# platine_gesamt_V05.net
KiCad netlist of a schematic drawn in EAGLE
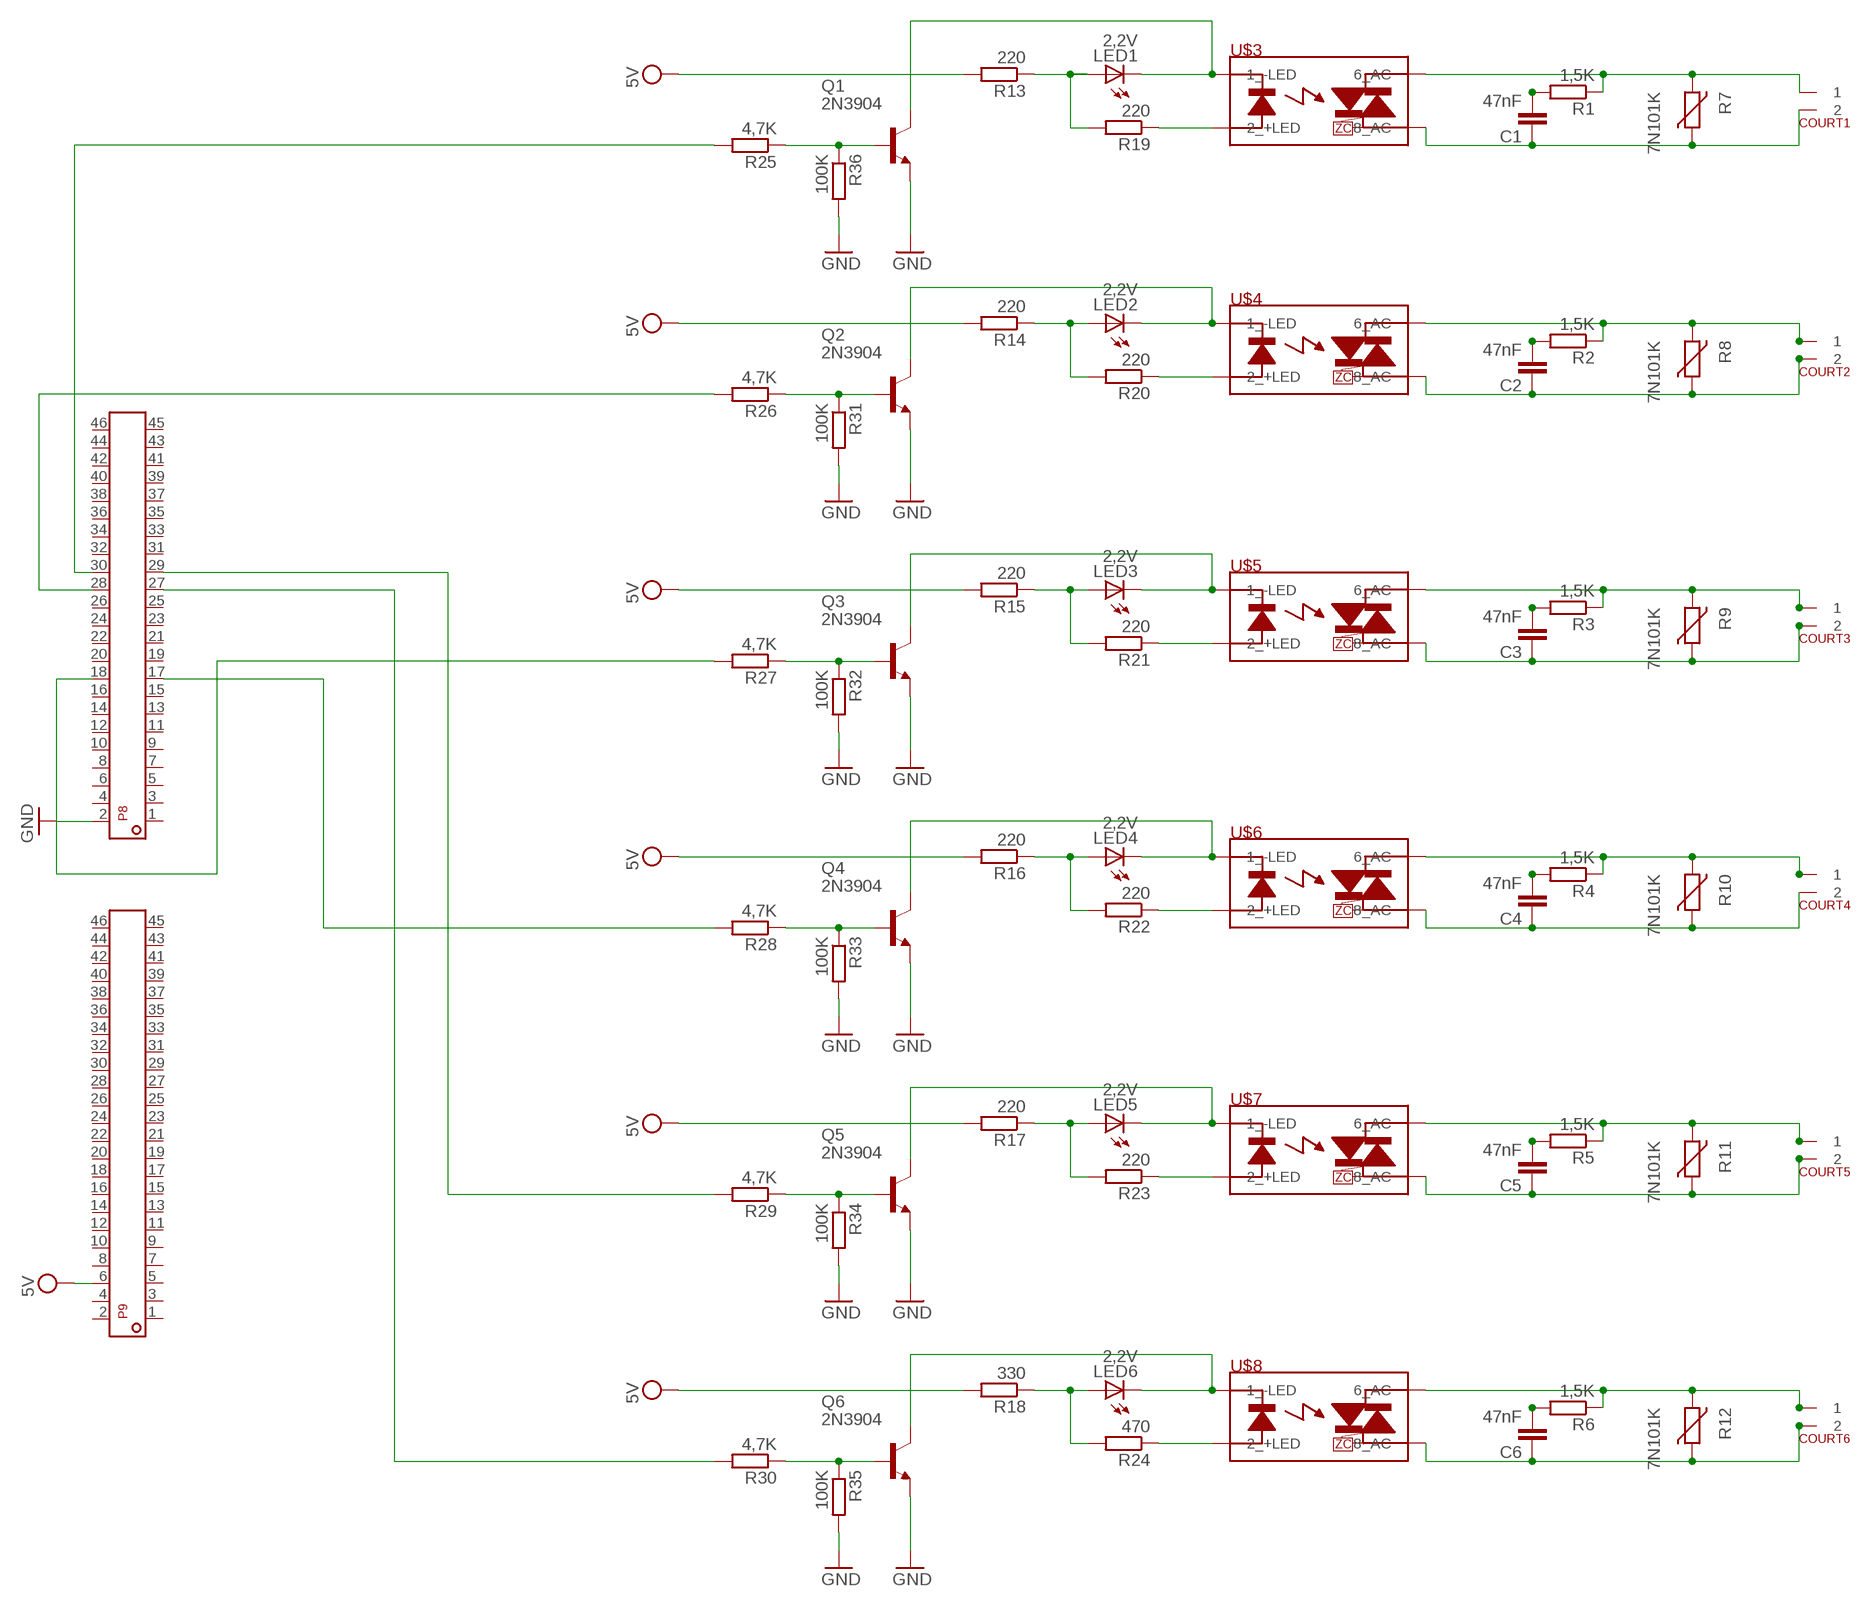
[diagram p0: schematic, sheet 1]

(export (version "E")
  (design (tool "Eeschema 10.0.6"))
  (components
    (comp (ref "C1")
      (value "47nF")
      (footprint "eagle-import:C7.5B3")
      (libsource (lib "eagle-import") (part "C7.5/3"))
    )
    (comp (ref "C2")
      (value "47nF")
      (footprint "eagle-import:C7.5B3")
      (libsource (lib "eagle-import") (part "C7.5/3"))
    )
    (comp (ref "C3")
      (value "47nF")
      (footprint "eagle-import:C7.5B3")
      (libsource (lib "eagle-import") (part "C7.5/3"))
    )
    (comp (ref "C4")
      (value "47nF")
      (footprint "eagle-import:C7.5B3")
      (libsource (lib "eagle-import") (part "C7.5/3"))
    )
    (comp (ref "C5")
      (value "47nF")
      (footprint "eagle-import:C7.5B3")
      (libsource (lib "eagle-import") (part "C7.5/3"))
    )
    (comp (ref "C6")
      (value "47nF")
      (footprint "eagle-import:C7.5B3")
      (libsource (lib "eagle-import") (part "C7.5/3"))
    )
    (comp (ref "COURT1")
      (value "KLEMMENBLOCK_2POL")
      (footprint "eagle-import:KLEMMENBLOCK_2POL")
      (libsource (lib "eagle-import") (part "KLEMMENBLOCK_2POL"))
    )
    (comp (ref "COURT2")
      (value "KLEMMENBLOCK_2POL")
      (footprint "eagle-import:KLEMMENBLOCK_2POL")
      (libsource (lib "eagle-import") (part "KLEMMENBLOCK_2POL"))
    )
    (comp (ref "COURT3")
      (value "KLEMMENBLOCK_2POL")
      (footprint "eagle-import:KLEMMENBLOCK_2POL")
      (libsource (lib "eagle-import") (part "KLEMMENBLOCK_2POL"))
    )
    (comp (ref "COURT4")
      (value "KLEMMENBLOCK_2POL")
      (footprint "eagle-import:KLEMMENBLOCK_2POL")
      (libsource (lib "eagle-import") (part "KLEMMENBLOCK_2POL"))
    )
    (comp (ref "COURT5")
      (value "KLEMMENBLOCK_2POL")
      (footprint "eagle-import:KLEMMENBLOCK_2POL")
      (libsource (lib "eagle-import") (part "KLEMMENBLOCK_2POL"))
    )
    (comp (ref "COURT6")
      (value "KLEMMENBLOCK_2POL")
      (footprint "eagle-import:KLEMMENBLOCK_2POL")
      (libsource (lib "eagle-import") (part "KLEMMENBLOCK_2POL"))
    )
    (comp (ref "LED1")
      (value "2,2V")
      (footprint "eagle-import:LED5MM")
      (libsource (lib "eagle-import") (part "LED5MM"))
    )
    (comp (ref "LED2")
      (value "2,2V")
      (footprint "eagle-import:LED5MM")
      (libsource (lib "eagle-import") (part "LED5MM"))
    )
    (comp (ref "LED3")
      (value "2,2V")
      (footprint "eagle-import:LED5MM")
      (libsource (lib "eagle-import") (part "LED5MM"))
    )
    (comp (ref "LED4")
      (value "2,2V")
      (footprint "eagle-import:LED5MM")
      (libsource (lib "eagle-import") (part "LED5MM"))
    )
    (comp (ref "LED5")
      (value "2,2V")
      (footprint "eagle-import:LED5MM")
      (libsource (lib "eagle-import") (part "LED5MM"))
    )
    (comp (ref "LED6")
      (value "2,2V")
      (footprint "eagle-import:LED5MM")
      (libsource (lib "eagle-import") (part "LED5MM"))
    )
    (comp (ref "P8")
      (value "FEMALE_HEADER_2X23")
      (footprint "eagle-import:FE23-2W")
      (libsource (lib "eagle-import") (part "FEMALE_HEADER_2X23"))
    )
    (comp (ref "P9")
      (value "FEMALE_HEADER_2X23")
      (footprint "eagle-import:FE23-2W")
      (libsource (lib "eagle-import") (part "FEMALE_HEADER_2X23"))
    )
    (comp (ref "Q1")
      (value "2N3904")
      (footprint "eagle-import:TO92")
      (libsource (lib "eagle-import") (part "2N3904"))
    )
    (comp (ref "Q2")
      (value "2N3904")
      (footprint "eagle-import:TO92")
      (libsource (lib "eagle-import") (part "2N3904"))
    )
    (comp (ref "Q3")
      (value "2N3904")
      (footprint "eagle-import:TO92")
      (libsource (lib "eagle-import") (part "2N3904"))
    )
    (comp (ref "Q4")
      (value "2N3904")
      (footprint "eagle-import:TO92")
      (libsource (lib "eagle-import") (part "2N3904"))
    )
    (comp (ref "Q5")
      (value "2N3904")
      (footprint "eagle-import:TO92")
      (libsource (lib "eagle-import") (part "2N3904"))
    )
    (comp (ref "Q6")
      (value "2N3904")
      (footprint "eagle-import:TO92")
      (libsource (lib "eagle-import") (part "2N3904"))
    )
    (comp (ref "R1")
      (value "1,5K")
      (footprint "eagle-import:0204_7")
      (libsource (lib "eagle-import") (part "R-EU_0204/7"))
    )
    (comp (ref "R2")
      (value "1,5K")
      (footprint "eagle-import:0204_7")
      (libsource (lib "eagle-import") (part "R-EU_0204/7"))
    )
    (comp (ref "R3")
      (value "1,5K")
      (footprint "eagle-import:0204_7")
      (libsource (lib "eagle-import") (part "R-EU_0204/7"))
    )
    (comp (ref "R4")
      (value "1,5K")
      (footprint "eagle-import:0204_7")
      (libsource (lib "eagle-import") (part "R-EU_0204/7"))
    )
    (comp (ref "R5")
      (value "1,5K")
      (footprint "eagle-import:0204_7")
      (libsource (lib "eagle-import") (part "R-EU_0204/7"))
    )
    (comp (ref "R6")
      (value "1,5K")
      (footprint "eagle-import:0204_7")
      (libsource (lib "eagle-import") (part "R-EU_0204/7"))
    )
    (comp (ref "R7")
      (value "7N101K")
      (footprint "eagle-import:R-5")
      (libsource (lib "eagle-import") (part "VARISTOR-5"))
    )
    (comp (ref "R8")
      (value "7N101K")
      (footprint "eagle-import:R-5")
      (libsource (lib "eagle-import") (part "VARISTOR-5"))
    )
    (comp (ref "R9")
      (value "7N101K")
      (footprint "eagle-import:R-5")
      (libsource (lib "eagle-import") (part "VARISTOR-5"))
    )
    (comp (ref "R10")
      (value "7N101K")
      (footprint "eagle-import:R-5")
      (libsource (lib "eagle-import") (part "VARISTOR-5"))
    )
    (comp (ref "R11")
      (value "7N101K")
      (footprint "eagle-import:R-5")
      (libsource (lib "eagle-import") (part "VARISTOR-5"))
    )
    (comp (ref "R12")
      (value "7N101K")
      (footprint "eagle-import:R-5")
      (libsource (lib "eagle-import") (part "VARISTOR-5"))
    )
    (comp (ref "R13")
      (value "220")
      (footprint "eagle-import:0204_7")
      (libsource (lib "eagle-import") (part "R-EU_0204/7"))
    )
    (comp (ref "R14")
      (value "220")
      (footprint "eagle-import:0204_7")
      (libsource (lib "eagle-import") (part "R-EU_0204/7"))
    )
    (comp (ref "R15")
      (value "220")
      (footprint "eagle-import:0204_7")
      (libsource (lib "eagle-import") (part "R-EU_0204/7"))
    )
    (comp (ref "R16")
      (value "220")
      (footprint "eagle-import:0204_7")
      (libsource (lib "eagle-import") (part "R-EU_0204/7"))
    )
    (comp (ref "R17")
      (value "220")
      (footprint "eagle-import:0204_7")
      (libsource (lib "eagle-import") (part "R-EU_0204/7"))
    )
    (comp (ref "R18")
      (value "330")
      (footprint "eagle-import:0204_7")
      (libsource (lib "eagle-import") (part "R-EU_0204/7"))
    )
    (comp (ref "R19")
      (value "220")
      (footprint "eagle-import:0204_7")
      (libsource (lib "eagle-import") (part "R-EU_0204/7"))
    )
    (comp (ref "R20")
      (value "220")
      (footprint "eagle-import:0204_7")
      (libsource (lib "eagle-import") (part "R-EU_0204/7"))
    )
    (comp (ref "R21")
      (value "220")
      (footprint "eagle-import:0204_7")
      (libsource (lib "eagle-import") (part "R-EU_0204/7"))
    )
    (comp (ref "R22")
      (value "220")
      (footprint "eagle-import:0204_7")
      (libsource (lib "eagle-import") (part "R-EU_0204/7"))
    )
    (comp (ref "R23")
      (value "220")
      (footprint "eagle-import:0204_7")
      (libsource (lib "eagle-import") (part "R-EU_0204/7"))
    )
    (comp (ref "R24")
      (value "470")
      (footprint "eagle-import:0204_7")
      (libsource (lib "eagle-import") (part "R-EU_0204/7"))
    )
    (comp (ref "R25")
      (value "4,7K")
      (footprint "eagle-import:0204_7")
      (libsource (lib "eagle-import") (part "R-EU_0204/7"))
    )
    (comp (ref "R26")
      (value "4,7K")
      (footprint "eagle-import:0204_7")
      (libsource (lib "eagle-import") (part "R-EU_0204/7"))
    )
    (comp (ref "R27")
      (value "4,7K")
      (footprint "eagle-import:0204_7")
      (libsource (lib "eagle-import") (part "R-EU_0204/7"))
    )
    (comp (ref "R28")
      (value "4,7K")
      (footprint "eagle-import:0204_7")
      (libsource (lib "eagle-import") (part "R-EU_0204/7"))
    )
    (comp (ref "R29")
      (value "4,7K")
      (footprint "eagle-import:0204_7")
      (libsource (lib "eagle-import") (part "R-EU_0204/7"))
    )
    (comp (ref "R30")
      (value "4,7K")
      (footprint "eagle-import:0204_7")
      (libsource (lib "eagle-import") (part "R-EU_0204/7"))
    )
    (comp (ref "R31")
      (value "100K")
      (footprint "eagle-import:0204_7")
      (libsource (lib "eagle-import") (part "R-EU_0204/7"))
    )
    (comp (ref "R32")
      (value "100K")
      (footprint "eagle-import:0204_7")
      (libsource (lib "eagle-import") (part "R-EU_0204/7"))
    )
    (comp (ref "R33")
      (value "100K")
      (footprint "eagle-import:0204_7")
      (libsource (lib "eagle-import") (part "R-EU_0204/7"))
    )
    (comp (ref "R34")
      (value "100K")
      (footprint "eagle-import:0204_7")
      (libsource (lib "eagle-import") (part "R-EU_0204/7"))
    )
    (comp (ref "R35")
      (value "100K")
      (footprint "eagle-import:0204_7")
      (libsource (lib "eagle-import") (part "R-EU_0204/7"))
    )
    (comp (ref "R36")
      (value "100K")
      (footprint "eagle-import:0204_7")
      (libsource (lib "eagle-import") (part "R-EU_0204/7"))
    )
    (comp (ref "U$3")
      (value "IXYS_PS1201_SSRSIP4/8")
      (footprint "eagle-import:S202S02")
      (libsource (lib "eagle-import") (part "IXYS_PS1201_SSRSIP4/8"))
    )
    (comp (ref "U$4")
      (value "IXYS_PS1201_SSRSIP4/8")
      (footprint "eagle-import:S202S02")
      (libsource (lib "eagle-import") (part "IXYS_PS1201_SSRSIP4/8"))
    )
    (comp (ref "U$5")
      (value "IXYS_PS1201_SSRSIP4/8")
      (footprint "eagle-import:S202S02")
      (libsource (lib "eagle-import") (part "IXYS_PS1201_SSRSIP4/8"))
    )
    (comp (ref "U$6")
      (value "IXYS_PS1201_SSRSIP4/8")
      (footprint "eagle-import:S202S02")
      (libsource (lib "eagle-import") (part "IXYS_PS1201_SSRSIP4/8"))
    )
    (comp (ref "U$7")
      (value "IXYS_PS1201_SSRSIP4/8")
      (footprint "eagle-import:S202S02")
      (libsource (lib "eagle-import") (part "IXYS_PS1201_SSRSIP4/8"))
    )
    (comp (ref "U$8")
      (value "IXYS_PS1201_SSRSIP4/8")
      (footprint "eagle-import:S202S02")
      (libsource (lib "eagle-import") (part "IXYS_PS1201_SSRSIP4/8"))
    )
  )
  (nets
    (net (code "1") (name "5V") (class "Default")
      (node (ref "P9") (pin "6") (pinfunction "6_6") (pintype "bidirectional"))
      (node (ref "R13") (pin "2") (pinfunction "2_2") (pintype "passive"))
      (node (ref "R14") (pin "2") (pinfunction "2_2") (pintype "passive"))
      (node (ref "R15") (pin "2") (pinfunction "2_2") (pintype "passive"))
      (node (ref "R16") (pin "2") (pinfunction "2_2") (pintype "passive"))
      (node (ref "R17") (pin "2") (pinfunction "2_2") (pintype "passive"))
      (node (ref "R18") (pin "2") (pinfunction "2_2") (pintype "passive"))
    )
    (net (code "2") (name "GND") (class "Default")
      (node (ref "P8") (pin "2") (pinfunction "2_2") (pintype "bidirectional"))
      (node (ref "Q1") (pin "3") (pinfunction "E_3") (pintype "passive"))
      (node (ref "Q2") (pin "3") (pinfunction "E_3") (pintype "passive"))
      (node (ref "Q3") (pin "3") (pinfunction "E_3") (pintype "passive"))
      (node (ref "Q4") (pin "3") (pinfunction "E_3") (pintype "passive"))
      (node (ref "Q5") (pin "3") (pinfunction "E_3") (pintype "passive"))
      (node (ref "Q6") (pin "3") (pinfunction "E_3") (pintype "passive"))
      (node (ref "R31") (pin "2") (pinfunction "2_2") (pintype "passive"))
      (node (ref "R32") (pin "2") (pinfunction "2_2") (pintype "passive"))
      (node (ref "R33") (pin "2") (pinfunction "2_2") (pintype "passive"))
      (node (ref "R34") (pin "2") (pinfunction "2_2") (pintype "passive"))
      (node (ref "R35") (pin "2") (pinfunction "2_2") (pintype "passive"))
      (node (ref "R36") (pin "2") (pinfunction "2_2") (pintype "passive"))
    )
    (net (code "3") (name "Net-(C1-Pad2)") (class "Default")
      (node (ref "C1") (pin "2") (pinfunction "2_2") (pintype "passive"))
      (node (ref "R1") (pin "2") (pinfunction "2_2") (pintype "passive"))
    )
    (net (code "4") (name "Net-(C2-Pad2)") (class "Default")
      (node (ref "C2") (pin "2") (pinfunction "2_2") (pintype "passive"))
      (node (ref "R2") (pin "2") (pinfunction "2_2") (pintype "passive"))
    )
    (net (code "5") (name "Net-(C3-Pad2)") (class "Default")
      (node (ref "C3") (pin "2") (pinfunction "2_2") (pintype "passive"))
      (node (ref "R3") (pin "2") (pinfunction "2_2") (pintype "passive"))
    )
    (net (code "6") (name "Net-(C4-Pad2)") (class "Default")
      (node (ref "C4") (pin "2") (pinfunction "2_2") (pintype "passive"))
      (node (ref "R4") (pin "2") (pinfunction "2_2") (pintype "passive"))
    )
    (net (code "7") (name "Net-(C5-Pad2)") (class "Default")
      (node (ref "C5") (pin "2") (pinfunction "2_2") (pintype "passive"))
      (node (ref "R5") (pin "2") (pinfunction "2_2") (pintype "passive"))
    )
    (net (code "8") (name "Net-(C6-Pad2)") (class "Default")
      (node (ref "C6") (pin "2") (pinfunction "2_2") (pintype "passive"))
      (node (ref "R6") (pin "2") (pinfunction "2_2") (pintype "passive"))
    )
    (net (code "9") (name "Net-(LED1-C)") (class "Default")
      (node (ref "LED1") (pin "K") (pinfunction "C_K") (pintype "passive"))
      (node (ref "Q1") (pin "1") (pinfunction "C_1") (pintype "passive"))
      (node (ref "U$3") (pin "1") (pinfunction "1_-LED_1") (pintype "bidirectional"))
    )
    (net (code "10") (name "Net-(LED1-PadA)") (class "Default")
      (node (ref "LED1") (pin "A") (pinfunction "A_A") (pintype "passive"))
      (node (ref "R13") (pin "1") (pinfunction "1_1") (pintype "passive"))
      (node (ref "R19") (pin "2") (pinfunction "2_2") (pintype "passive"))
    )
    (net (code "11") (name "Net-(LED2-C)") (class "Default")
      (node (ref "LED2") (pin "K") (pinfunction "C_K") (pintype "passive"))
      (node (ref "Q2") (pin "1") (pinfunction "C_1") (pintype "passive"))
      (node (ref "U$4") (pin "1") (pinfunction "1_-LED_1") (pintype "bidirectional"))
    )
    (net (code "12") (name "Net-(LED2-PadA)") (class "Default")
      (node (ref "LED2") (pin "A") (pinfunction "A_A") (pintype "passive"))
      (node (ref "R14") (pin "1") (pinfunction "1_1") (pintype "passive"))
      (node (ref "R20") (pin "2") (pinfunction "2_2") (pintype "passive"))
    )
    (net (code "13") (name "Net-(LED3-C)") (class "Default")
      (node (ref "LED3") (pin "K") (pinfunction "C_K") (pintype "passive"))
      (node (ref "Q3") (pin "1") (pinfunction "C_1") (pintype "passive"))
      (node (ref "U$5") (pin "1") (pinfunction "1_-LED_1") (pintype "bidirectional"))
    )
    (net (code "14") (name "Net-(LED3-PadA)") (class "Default")
      (node (ref "LED3") (pin "A") (pinfunction "A_A") (pintype "passive"))
      (node (ref "R15") (pin "1") (pinfunction "1_1") (pintype "passive"))
      (node (ref "R21") (pin "2") (pinfunction "2_2") (pintype "passive"))
    )
    (net (code "15") (name "Net-(LED4-C)") (class "Default")
      (node (ref "LED4") (pin "K") (pinfunction "C_K") (pintype "passive"))
      (node (ref "Q4") (pin "1") (pinfunction "C_1") (pintype "passive"))
      (node (ref "U$6") (pin "1") (pinfunction "1_-LED_1") (pintype "bidirectional"))
    )
    (net (code "16") (name "Net-(LED4-PadA)") (class "Default")
      (node (ref "LED4") (pin "A") (pinfunction "A_A") (pintype "passive"))
      (node (ref "R16") (pin "1") (pinfunction "1_1") (pintype "passive"))
      (node (ref "R22") (pin "2") (pinfunction "2_2") (pintype "passive"))
    )
    (net (code "17") (name "Net-(LED5-C)") (class "Default")
      (node (ref "LED5") (pin "K") (pinfunction "C_K") (pintype "passive"))
      (node (ref "Q5") (pin "1") (pinfunction "C_1") (pintype "passive"))
      (node (ref "U$7") (pin "1") (pinfunction "1_-LED_1") (pintype "bidirectional"))
    )
    (net (code "18") (name "Net-(LED5-PadA)") (class "Default")
      (node (ref "LED5") (pin "A") (pinfunction "A_A") (pintype "passive"))
      (node (ref "R17") (pin "1") (pinfunction "1_1") (pintype "passive"))
      (node (ref "R23") (pin "2") (pinfunction "2_2") (pintype "passive"))
    )
    (net (code "19") (name "Net-(LED6-C)") (class "Default")
      (node (ref "LED6") (pin "K") (pinfunction "C_K") (pintype "passive"))
      (node (ref "Q6") (pin "1") (pinfunction "C_1") (pintype "passive"))
      (node (ref "U$8") (pin "1") (pinfunction "1_-LED_1") (pintype "bidirectional"))
    )
    (net (code "20") (name "Net-(LED6-PadA)") (class "Default")
      (node (ref "LED6") (pin "A") (pinfunction "A_A") (pintype "passive"))
      (node (ref "R18") (pin "1") (pinfunction "1_1") (pintype "passive"))
      (node (ref "R24") (pin "2") (pinfunction "2_2") (pintype "passive"))
    )
    (net (code "21") (name "Net-(P8-Pad17)") (class "Default")
      (node (ref "P8") (pin "17") (pinfunction "17_17") (pintype "bidirectional"))
      (node (ref "R28") (pin "2") (pinfunction "2_2") (pintype "passive"))
    )
    (net (code "22") (name "Net-(P8-Pad18)") (class "Default")
      (node (ref "P8") (pin "18") (pinfunction "18_18") (pintype "bidirectional"))
      (node (ref "R27") (pin "2") (pinfunction "2_2") (pintype "passive"))
    )
    (net (code "23") (name "Net-(P8-Pad27)") (class "Default")
      (node (ref "P8") (pin "27") (pinfunction "27_27") (pintype "bidirectional"))
      (node (ref "R30") (pin "2") (pinfunction "2_2") (pintype "passive"))
    )
    (net (code "24") (name "Net-(P8-Pad28)") (class "Default")
      (node (ref "P8") (pin "28") (pinfunction "28_28") (pintype "bidirectional"))
      (node (ref "R26") (pin "2") (pinfunction "2_2") (pintype "passive"))
    )
    (net (code "25") (name "Net-(P8-Pad29)") (class "Default")
      (node (ref "P8") (pin "29") (pinfunction "29_29") (pintype "bidirectional"))
      (node (ref "R29") (pin "2") (pinfunction "2_2") (pintype "passive"))
    )
    (net (code "26") (name "Net-(P8-Pad30)") (class "Default")
      (node (ref "P8") (pin "30") (pinfunction "30_30") (pintype "bidirectional"))
      (node (ref "R25") (pin "2") (pinfunction "2_2") (pintype "passive"))
    )
    (net (code "27") (name "Net-(Q1-B)") (class "Default")
      (node (ref "Q1") (pin "2") (pinfunction "B_2") (pintype "passive"))
      (node (ref "R25") (pin "1") (pinfunction "1_1") (pintype "passive"))
      (node (ref "R36") (pin "1") (pinfunction "1_1") (pintype "passive"))
    )
    (net (code "28") (name "Net-(Q2-B)") (class "Default")
      (node (ref "Q2") (pin "2") (pinfunction "B_2") (pintype "passive"))
      (node (ref "R26") (pin "1") (pinfunction "1_1") (pintype "passive"))
      (node (ref "R31") (pin "1") (pinfunction "1_1") (pintype "passive"))
    )
    (net (code "29") (name "Net-(Q3-B)") (class "Default")
      (node (ref "Q3") (pin "2") (pinfunction "B_2") (pintype "passive"))
      (node (ref "R27") (pin "1") (pinfunction "1_1") (pintype "passive"))
      (node (ref "R32") (pin "1") (pinfunction "1_1") (pintype "passive"))
    )
    (net (code "30") (name "Net-(Q4-B)") (class "Default")
      (node (ref "Q4") (pin "2") (pinfunction "B_2") (pintype "passive"))
      (node (ref "R28") (pin "1") (pinfunction "1_1") (pintype "passive"))
      (node (ref "R33") (pin "1") (pinfunction "1_1") (pintype "passive"))
    )
    (net (code "31") (name "Net-(Q5-B)") (class "Default")
      (node (ref "Q5") (pin "2") (pinfunction "B_2") (pintype "passive"))
      (node (ref "R29") (pin "1") (pinfunction "1_1") (pintype "passive"))
      (node (ref "R34") (pin "1") (pinfunction "1_1") (pintype "passive"))
    )
    (net (code "32") (name "Net-(Q6-B)") (class "Default")
      (node (ref "Q6") (pin "2") (pinfunction "B_2") (pintype "passive"))
      (node (ref "R30") (pin "1") (pinfunction "1_1") (pintype "passive"))
      (node (ref "R35") (pin "1") (pinfunction "1_1") (pintype "passive"))
    )
    (net (code "33") (name "Net-(U$3-2_+LED)") (class "Default")
      (node (ref "R19") (pin "1") (pinfunction "1_1") (pintype "passive"))
      (node (ref "U$3") (pin "2") (pinfunction "2_+LED_2") (pintype "bidirectional"))
    )
    (net (code "34") (name "Net-(U$3-6_AC)") (class "Default")
      (node (ref "COURT1") (pin "1") (pinfunction "1_1") (pintype "bidirectional"))
      (node (ref "R1") (pin "1") (pinfunction "1_1") (pintype "passive"))
      (node (ref "R7") (pin "2") (pinfunction "2_2") (pintype "passive"))
      (node (ref "U$3") (pin "6") (pinfunction "6_AC_6") (pintype "bidirectional"))
    )
    (net (code "35") (name "Net-(U$3-8_AC)") (class "Default")
      (node (ref "C1") (pin "1") (pinfunction "1_1") (pintype "passive"))
      (node (ref "COURT1") (pin "2") (pinfunction "2_2") (pintype "bidirectional"))
      (node (ref "R7") (pin "1") (pinfunction "1_1") (pintype "passive"))
      (node (ref "U$3") (pin "8") (pinfunction "8_AC_8") (pintype "bidirectional"))
    )
    (net (code "36") (name "Net-(U$4-2_+LED)") (class "Default")
      (node (ref "R20") (pin "1") (pinfunction "1_1") (pintype "passive"))
      (node (ref "U$4") (pin "2") (pinfunction "2_+LED_2") (pintype "bidirectional"))
    )
    (net (code "37") (name "Net-(U$4-6_AC)") (class "Default")
      (node (ref "COURT2") (pin "1") (pinfunction "1_1") (pintype "bidirectional"))
      (node (ref "R2") (pin "1") (pinfunction "1_1") (pintype "passive"))
      (node (ref "R8") (pin "2") (pinfunction "2_2") (pintype "passive"))
      (node (ref "U$4") (pin "6") (pinfunction "6_AC_6") (pintype "bidirectional"))
    )
    (net (code "38") (name "Net-(U$4-8_AC)") (class "Default")
      (node (ref "C2") (pin "1") (pinfunction "1_1") (pintype "passive"))
      (node (ref "COURT2") (pin "2") (pinfunction "2_2") (pintype "bidirectional"))
      (node (ref "R8") (pin "1") (pinfunction "1_1") (pintype "passive"))
      (node (ref "U$4") (pin "8") (pinfunction "8_AC_8") (pintype "bidirectional"))
    )
    (net (code "39") (name "Net-(U$5-2_+LED)") (class "Default")
      (node (ref "R21") (pin "1") (pinfunction "1_1") (pintype "passive"))
      (node (ref "U$5") (pin "2") (pinfunction "2_+LED_2") (pintype "bidirectional"))
    )
    (net (code "40") (name "Net-(U$5-6_AC)") (class "Default")
      (node (ref "COURT3") (pin "1") (pinfunction "1_1") (pintype "bidirectional"))
      (node (ref "R3") (pin "1") (pinfunction "1_1") (pintype "passive"))
      (node (ref "R9") (pin "2") (pinfunction "2_2") (pintype "passive"))
      (node (ref "U$5") (pin "6") (pinfunction "6_AC_6") (pintype "bidirectional"))
    )
    (net (code "41") (name "Net-(U$5-8_AC)") (class "Default")
      (node (ref "C3") (pin "1") (pinfunction "1_1") (pintype "passive"))
      (node (ref "COURT3") (pin "2") (pinfunction "2_2") (pintype "bidirectional"))
      (node (ref "R9") (pin "1") (pinfunction "1_1") (pintype "passive"))
      (node (ref "U$5") (pin "8") (pinfunction "8_AC_8") (pintype "bidirectional"))
    )
    (net (code "42") (name "Net-(U$6-2_+LED)") (class "Default")
      (node (ref "R22") (pin "1") (pinfunction "1_1") (pintype "passive"))
      (node (ref "U$6") (pin "2") (pinfunction "2_+LED_2") (pintype "bidirectional"))
    )
    (net (code "43") (name "Net-(U$6-6_AC)") (class "Default")
      (node (ref "COURT4") (pin "1") (pinfunction "1_1") (pintype "bidirectional"))
      (node (ref "R10") (pin "2") (pinfunction "2_2") (pintype "passive"))
      (node (ref "R4") (pin "1") (pinfunction "1_1") (pintype "passive"))
      (node (ref "U$6") (pin "6") (pinfunction "6_AC_6") (pintype "bidirectional"))
    )
    (net (code "44") (name "Net-(U$6-8_AC)") (class "Default")
      (node (ref "C4") (pin "1") (pinfunction "1_1") (pintype "passive"))
      (node (ref "COURT4") (pin "2") (pinfunction "2_2") (pintype "bidirectional"))
      (node (ref "R10") (pin "1") (pinfunction "1_1") (pintype "passive"))
      (node (ref "U$6") (pin "8") (pinfunction "8_AC_8") (pintype "bidirectional"))
    )
    (net (code "45") (name "Net-(U$7-2_+LED)") (class "Default")
      (node (ref "R23") (pin "1") (pinfunction "1_1") (pintype "passive"))
      (node (ref "U$7") (pin "2") (pinfunction "2_+LED_2") (pintype "bidirectional"))
    )
    (net (code "46") (name "Net-(U$7-6_AC)") (class "Default")
      (node (ref "COURT5") (pin "1") (pinfunction "1_1") (pintype "bidirectional"))
      (node (ref "R11") (pin "2") (pinfunction "2_2") (pintype "passive"))
      (node (ref "R5") (pin "1") (pinfunction "1_1") (pintype "passive"))
      (node (ref "U$7") (pin "6") (pinfunction "6_AC_6") (pintype "bidirectional"))
    )
    (net (code "47") (name "Net-(U$7-8_AC)") (class "Default")
      (node (ref "C5") (pin "1") (pinfunction "1_1") (pintype "passive"))
      (node (ref "COURT5") (pin "2") (pinfunction "2_2") (pintype "bidirectional"))
      (node (ref "R11") (pin "1") (pinfunction "1_1") (pintype "passive"))
      (node (ref "U$7") (pin "8") (pinfunction "8_AC_8") (pintype "bidirectional"))
    )
    (net (code "48") (name "Net-(U$8-2_+LED)") (class "Default")
      (node (ref "R24") (pin "1") (pinfunction "1_1") (pintype "passive"))
      (node (ref "U$8") (pin "2") (pinfunction "2_+LED_2") (pintype "bidirectional"))
    )
    (net (code "49") (name "Net-(U$8-6_AC)") (class "Default")
      (node (ref "COURT6") (pin "1") (pinfunction "1_1") (pintype "bidirectional"))
      (node (ref "R12") (pin "2") (pinfunction "2_2") (pintype "passive"))
      (node (ref "R6") (pin "1") (pinfunction "1_1") (pintype "passive"))
      (node (ref "U$8") (pin "6") (pinfunction "6_AC_6") (pintype "bidirectional"))
    )
    (net (code "50") (name "Net-(U$8-8_AC)") (class "Default")
      (node (ref "C6") (pin "1") (pinfunction "1_1") (pintype "passive"))
      (node (ref "COURT6") (pin "2") (pinfunction "2_2") (pintype "bidirectional"))
      (node (ref "R12") (pin "1") (pinfunction "1_1") (pintype "passive"))
      (node (ref "U$8") (pin "8") (pinfunction "8_AC_8") (pintype "bidirectional"))
    )
    (net (code "51") (name "unconnected-(P8-Pad1)") (class "Default")
      (node (ref "P8") (pin "1") (pinfunction "1_1") (pintype "bidirectional"))
    )
    (net (code "52") (name "unconnected-(P8-Pad3)") (class "Default")
      (node (ref "P8") (pin "3") (pinfunction "3_3") (pintype "bidirectional"))
    )
    (net (code "53") (name "unconnected-(P8-Pad4)") (class "Default")
      (node (ref "P8") (pin "4") (pinfunction "4_4") (pintype "bidirectional"))
    )
    (net (code "54") (name "unconnected-(P8-Pad5)") (class "Default")
      (node (ref "P8") (pin "5") (pinfunction "5_5") (pintype "bidirectional"))
    )
    (net (code "55") (name "unconnected-(P8-Pad6)") (class "Default")
      (node (ref "P8") (pin "6") (pinfunction "6_6") (pintype "bidirectional"))
    )
    (net (code "56") (name "unconnected-(P8-Pad7)") (class "Default")
      (node (ref "P8") (pin "7") (pinfunction "7_7") (pintype "bidirectional"))
    )
    (net (code "57") (name "unconnected-(P8-Pad8)") (class "Default")
      (node (ref "P8") (pin "8") (pinfunction "8_8") (pintype "bidirectional"))
    )
    (net (code "58") (name "unconnected-(P8-Pad9)") (class "Default")
      (node (ref "P8") (pin "9") (pinfunction "9_9") (pintype "bidirectional"))
    )
    (net (code "59") (name "unconnected-(P8-Pad10)") (class "Default")
      (node (ref "P8") (pin "10") (pinfunction "10_10") (pintype "bidirectional"))
    )
    (net (code "60") (name "unconnected-(P8-Pad11)") (class "Default")
      (node (ref "P8") (pin "11") (pinfunction "11_11") (pintype "bidirectional"))
    )
    (net (code "61") (name "unconnected-(P8-Pad12)") (class "Default")
      (node (ref "P8") (pin "12") (pinfunction "12_12") (pintype "bidirectional"))
    )
    (net (code "62") (name "unconnected-(P8-Pad13)") (class "Default")
      (node (ref "P8") (pin "13") (pinfunction "13_13") (pintype "bidirectional"))
    )
    (net (code "63") (name "unconnected-(P8-Pad14)") (class "Default")
      (node (ref "P8") (pin "14") (pinfunction "14_14") (pintype "bidirectional"))
    )
    (net (code "64") (name "unconnected-(P8-Pad15)") (class "Default")
      (node (ref "P8") (pin "15") (pinfunction "15_15") (pintype "bidirectional"))
    )
    (net (code "65") (name "unconnected-(P8-Pad16)") (class "Default")
      (node (ref "P8") (pin "16") (pinfunction "16_16") (pintype "bidirectional"))
    )
    (net (code "66") (name "unconnected-(P8-Pad19)") (class "Default")
      (node (ref "P8") (pin "19") (pinfunction "19_19") (pintype "bidirectional"))
    )
    (net (code "67") (name "unconnected-(P8-Pad20)") (class "Default")
      (node (ref "P8") (pin "20") (pinfunction "20_20") (pintype "bidirectional"))
    )
    (net (code "68") (name "unconnected-(P8-Pad21)") (class "Default")
      (node (ref "P8") (pin "21") (pinfunction "21_21") (pintype "bidirectional"))
    )
    (net (code "69") (name "unconnected-(P8-Pad22)") (class "Default")
      (node (ref "P8") (pin "22") (pinfunction "22_22") (pintype "bidirectional"))
    )
    (net (code "70") (name "unconnected-(P8-Pad23)") (class "Default")
      (node (ref "P8") (pin "23") (pinfunction "23_23") (pintype "bidirectional"))
    )
    (net (code "71") (name "unconnected-(P8-Pad24)") (class "Default")
      (node (ref "P8") (pin "24") (pinfunction "24_24") (pintype "bidirectional"))
    )
    (net (code "72") (name "unconnected-(P8-Pad25)") (class "Default")
      (node (ref "P8") (pin "25") (pinfunction "25_25") (pintype "bidirectional"))
    )
    (net (code "73") (name "unconnected-(P8-Pad26)") (class "Default")
      (node (ref "P8") (pin "26") (pinfunction "26_26") (pintype "bidirectional"))
    )
    (net (code "74") (name "unconnected-(P8-Pad31)") (class "Default")
      (node (ref "P8") (pin "31") (pinfunction "31_31") (pintype "bidirectional"))
    )
    (net (code "75") (name "unconnected-(P8-Pad32)") (class "Default")
      (node (ref "P8") (pin "32") (pinfunction "32_32") (pintype "bidirectional"))
    )
    (net (code "76") (name "unconnected-(P8-Pad33)") (class "Default")
      (node (ref "P8") (pin "33") (pinfunction "33_33") (pintype "bidirectional"))
    )
    (net (code "77") (name "unconnected-(P8-Pad34)") (class "Default")
      (node (ref "P8") (pin "34") (pinfunction "34_34") (pintype "bidirectional"))
    )
    (net (code "78") (name "unconnected-(P8-Pad35)") (class "Default")
      (node (ref "P8") (pin "35") (pinfunction "35_35") (pintype "bidirectional"))
    )
    (net (code "79") (name "unconnected-(P8-Pad36)") (class "Default")
      (node (ref "P8") (pin "36") (pinfunction "36_36") (pintype "bidirectional"))
    )
    (net (code "80") (name "unconnected-(P8-Pad37)") (class "Default")
      (node (ref "P8") (pin "37") (pinfunction "37_37") (pintype "bidirectional"))
    )
    (net (code "81") (name "unconnected-(P8-Pad38)") (class "Default")
      (node (ref "P8") (pin "38") (pinfunction "38_38") (pintype "bidirectional"))
    )
    (net (code "82") (name "unconnected-(P8-Pad39)") (class "Default")
      (node (ref "P8") (pin "39") (pinfunction "39_39") (pintype "bidirectional"))
    )
    (net (code "83") (name "unconnected-(P8-Pad40)") (class "Default")
      (node (ref "P8") (pin "40") (pinfunction "40_40") (pintype "bidirectional"))
    )
    (net (code "84") (name "unconnected-(P8-Pad41)") (class "Default")
      (node (ref "P8") (pin "41") (pinfunction "41_41") (pintype "bidirectional"))
    )
    (net (code "85") (name "unconnected-(P8-Pad42)") (class "Default")
      (node (ref "P8") (pin "42") (pinfunction "42_42") (pintype "bidirectional"))
    )
    (net (code "86") (name "unconnected-(P8-Pad43)") (class "Default")
      (node (ref "P8") (pin "43") (pinfunction "43_43") (pintype "bidirectional"))
    )
    (net (code "87") (name "unconnected-(P8-Pad44)") (class "Default")
      (node (ref "P8") (pin "44") (pinfunction "44_44") (pintype "bidirectional"))
    )
    (net (code "88") (name "unconnected-(P8-Pad45)") (class "Default")
      (node (ref "P8") (pin "45") (pinfunction "45_45") (pintype "bidirectional"))
    )
    (net (code "89") (name "unconnected-(P8-Pad46)") (class "Default")
      (node (ref "P8") (pin "46") (pinfunction "46_46") (pintype "bidirectional"))
    )
    (net (code "90") (name "unconnected-(P9-Pad1)") (class "Default")
      (node (ref "P9") (pin "1") (pinfunction "1_1") (pintype "bidirectional"))
    )
    (net (code "91") (name "unconnected-(P9-Pad2)") (class "Default")
      (node (ref "P9") (pin "2") (pinfunction "2_2") (pintype "bidirectional"))
    )
    (net (code "92") (name "unconnected-(P9-Pad3)") (class "Default")
      (node (ref "P9") (pin "3") (pinfunction "3_3") (pintype "bidirectional"))
    )
    (net (code "93") (name "unconnected-(P9-Pad4)") (class "Default")
      (node (ref "P9") (pin "4") (pinfunction "4_4") (pintype "bidirectional"))
    )
    (net (code "94") (name "unconnected-(P9-Pad5)") (class "Default")
      (node (ref "P9") (pin "5") (pinfunction "5_5") (pintype "bidirectional"))
    )
    (net (code "95") (name "unconnected-(P9-Pad7)") (class "Default")
      (node (ref "P9") (pin "7") (pinfunction "7_7") (pintype "bidirectional"))
    )
    (net (code "96") (name "unconnected-(P9-Pad8)") (class "Default")
      (node (ref "P9") (pin "8") (pinfunction "8_8") (pintype "bidirectional"))
    )
    (net (code "97") (name "unconnected-(P9-Pad9)") (class "Default")
      (node (ref "P9") (pin "9") (pinfunction "9_9") (pintype "bidirectional"))
    )
    (net (code "98") (name "unconnected-(P9-Pad10)") (class "Default")
      (node (ref "P9") (pin "10") (pinfunction "10_10") (pintype "bidirectional"))
    )
    (net (code "99") (name "unconnected-(P9-Pad11)") (class "Default")
      (node (ref "P9") (pin "11") (pinfunction "11_11") (pintype "bidirectional"))
    )
    (net (code "100") (name "unconnected-(P9-Pad12)") (class "Default")
      (node (ref "P9") (pin "12") (pinfunction "12_12") (pintype "bidirectional"))
    )
    (net (code "101") (name "unconnected-(P9-Pad13)") (class "Default")
      (node (ref "P9") (pin "13") (pinfunction "13_13") (pintype "bidirectional"))
    )
    (net (code "102") (name "unconnected-(P9-Pad14)") (class "Default")
      (node (ref "P9") (pin "14") (pinfunction "14_14") (pintype "bidirectional"))
    )
    (net (code "103") (name "unconnected-(P9-Pad15)") (class "Default")
      (node (ref "P9") (pin "15") (pinfunction "15_15") (pintype "bidirectional"))
    )
    (net (code "104") (name "unconnected-(P9-Pad16)") (class "Default")
      (node (ref "P9") (pin "16") (pinfunction "16_16") (pintype "bidirectional"))
    )
    (net (code "105") (name "unconnected-(P9-Pad17)") (class "Default")
      (node (ref "P9") (pin "17") (pinfunction "17_17") (pintype "bidirectional"))
    )
    (net (code "106") (name "unconnected-(P9-Pad18)") (class "Default")
      (node (ref "P9") (pin "18") (pinfunction "18_18") (pintype "bidirectional"))
    )
    (net (code "107") (name "unconnected-(P9-Pad19)") (class "Default")
      (node (ref "P9") (pin "19") (pinfunction "19_19") (pintype "bidirectional"))
    )
    (net (code "108") (name "unconnected-(P9-Pad20)") (class "Default")
      (node (ref "P9") (pin "20") (pinfunction "20_20") (pintype "bidirectional"))
    )
    (net (code "109") (name "unconnected-(P9-Pad21)") (class "Default")
      (node (ref "P9") (pin "21") (pinfunction "21_21") (pintype "bidirectional"))
    )
    (net (code "110") (name "unconnected-(P9-Pad22)") (class "Default")
      (node (ref "P9") (pin "22") (pinfunction "22_22") (pintype "bidirectional"))
    )
    (net (code "111") (name "unconnected-(P9-Pad23)") (class "Default")
      (node (ref "P9") (pin "23") (pinfunction "23_23") (pintype "bidirectional"))
    )
    (net (code "112") (name "unconnected-(P9-Pad24)") (class "Default")
      (node (ref "P9") (pin "24") (pinfunction "24_24") (pintype "bidirectional"))
    )
    (net (code "113") (name "unconnected-(P9-Pad25)") (class "Default")
      (node (ref "P9") (pin "25") (pinfunction "25_25") (pintype "bidirectional"))
    )
    (net (code "114") (name "unconnected-(P9-Pad26)") (class "Default")
      (node (ref "P9") (pin "26") (pinfunction "26_26") (pintype "bidirectional"))
    )
    (net (code "115") (name "unconnected-(P9-Pad27)") (class "Default")
      (node (ref "P9") (pin "27") (pinfunction "27_27") (pintype "bidirectional"))
    )
    (net (code "116") (name "unconnected-(P9-Pad28)") (class "Default")
      (node (ref "P9") (pin "28") (pinfunction "28_28") (pintype "bidirectional"))
    )
    (net (code "117") (name "unconnected-(P9-Pad29)") (class "Default")
      (node (ref "P9") (pin "29") (pinfunction "29_29") (pintype "bidirectional"))
    )
    (net (code "118") (name "unconnected-(P9-Pad30)") (class "Default")
      (node (ref "P9") (pin "30") (pinfunction "30_30") (pintype "bidirectional"))
    )
    (net (code "119") (name "unconnected-(P9-Pad31)") (class "Default")
      (node (ref "P9") (pin "31") (pinfunction "31_31") (pintype "bidirectional"))
    )
    (net (code "120") (name "unconnected-(P9-Pad32)") (class "Default")
      (node (ref "P9") (pin "32") (pinfunction "32_32") (pintype "bidirectional"))
    )
    (net (code "121") (name "unconnected-(P9-Pad33)") (class "Default")
      (node (ref "P9") (pin "33") (pinfunction "33_33") (pintype "bidirectional"))
    )
    (net (code "122") (name "unconnected-(P9-Pad34)") (class "Default")
      (node (ref "P9") (pin "34") (pinfunction "34_34") (pintype "bidirectional"))
    )
    (net (code "123") (name "unconnected-(P9-Pad35)") (class "Default")
      (node (ref "P9") (pin "35") (pinfunction "35_35") (pintype "bidirectional"))
    )
    (net (code "124") (name "unconnected-(P9-Pad36)") (class "Default")
      (node (ref "P9") (pin "36") (pinfunction "36_36") (pintype "bidirectional"))
    )
    (net (code "125") (name "unconnected-(P9-Pad37)") (class "Default")
      (node (ref "P9") (pin "37") (pinfunction "37_37") (pintype "bidirectional"))
    )
    (net (code "126") (name "unconnected-(P9-Pad38)") (class "Default")
      (node (ref "P9") (pin "38") (pinfunction "38_38") (pintype "bidirectional"))
    )
    (net (code "127") (name "unconnected-(P9-Pad39)") (class "Default")
      (node (ref "P9") (pin "39") (pinfunction "39_39") (pintype "bidirectional"))
    )
    (net (code "128") (name "unconnected-(P9-Pad40)") (class "Default")
      (node (ref "P9") (pin "40") (pinfunction "40_40") (pintype "bidirectional"))
    )
    (net (code "129") (name "unconnected-(P9-Pad41)") (class "Default")
      (node (ref "P9") (pin "41") (pinfunction "41_41") (pintype "bidirectional"))
    )
    (net (code "130") (name "unconnected-(P9-Pad42)") (class "Default")
      (node (ref "P9") (pin "42") (pinfunction "42_42") (pintype "bidirectional"))
    )
    (net (code "131") (name "unconnected-(P9-Pad43)") (class "Default")
      (node (ref "P9") (pin "43") (pinfunction "43_43") (pintype "bidirectional"))
    )
    (net (code "132") (name "unconnected-(P9-Pad44)") (class "Default")
      (node (ref "P9") (pin "44") (pinfunction "44_44") (pintype "bidirectional"))
    )
    (net (code "133") (name "unconnected-(P9-Pad45)") (class "Default")
      (node (ref "P9") (pin "45") (pinfunction "45_45") (pintype "bidirectional"))
    )
    (net (code "134") (name "unconnected-(P9-Pad46)") (class "Default")
      (node (ref "P9") (pin "46") (pinfunction "46_46") (pintype "bidirectional"))
    )
  )
)
